# improved_circuit.net
KiCad netlist of a schematic drawn in EAGLE
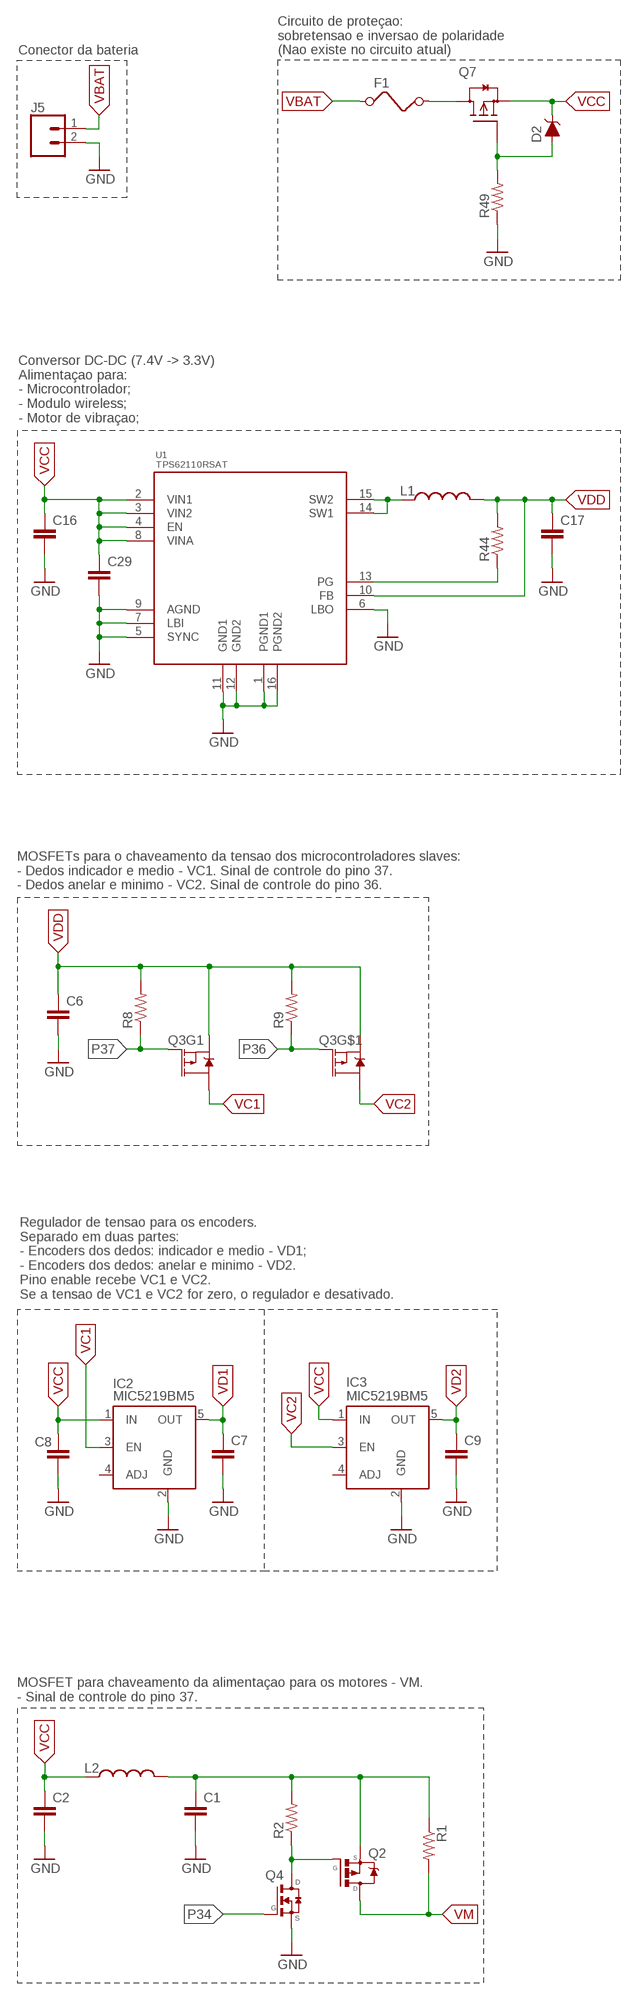
[diagram p0: schematic, sheet 1, part 1 of 2]
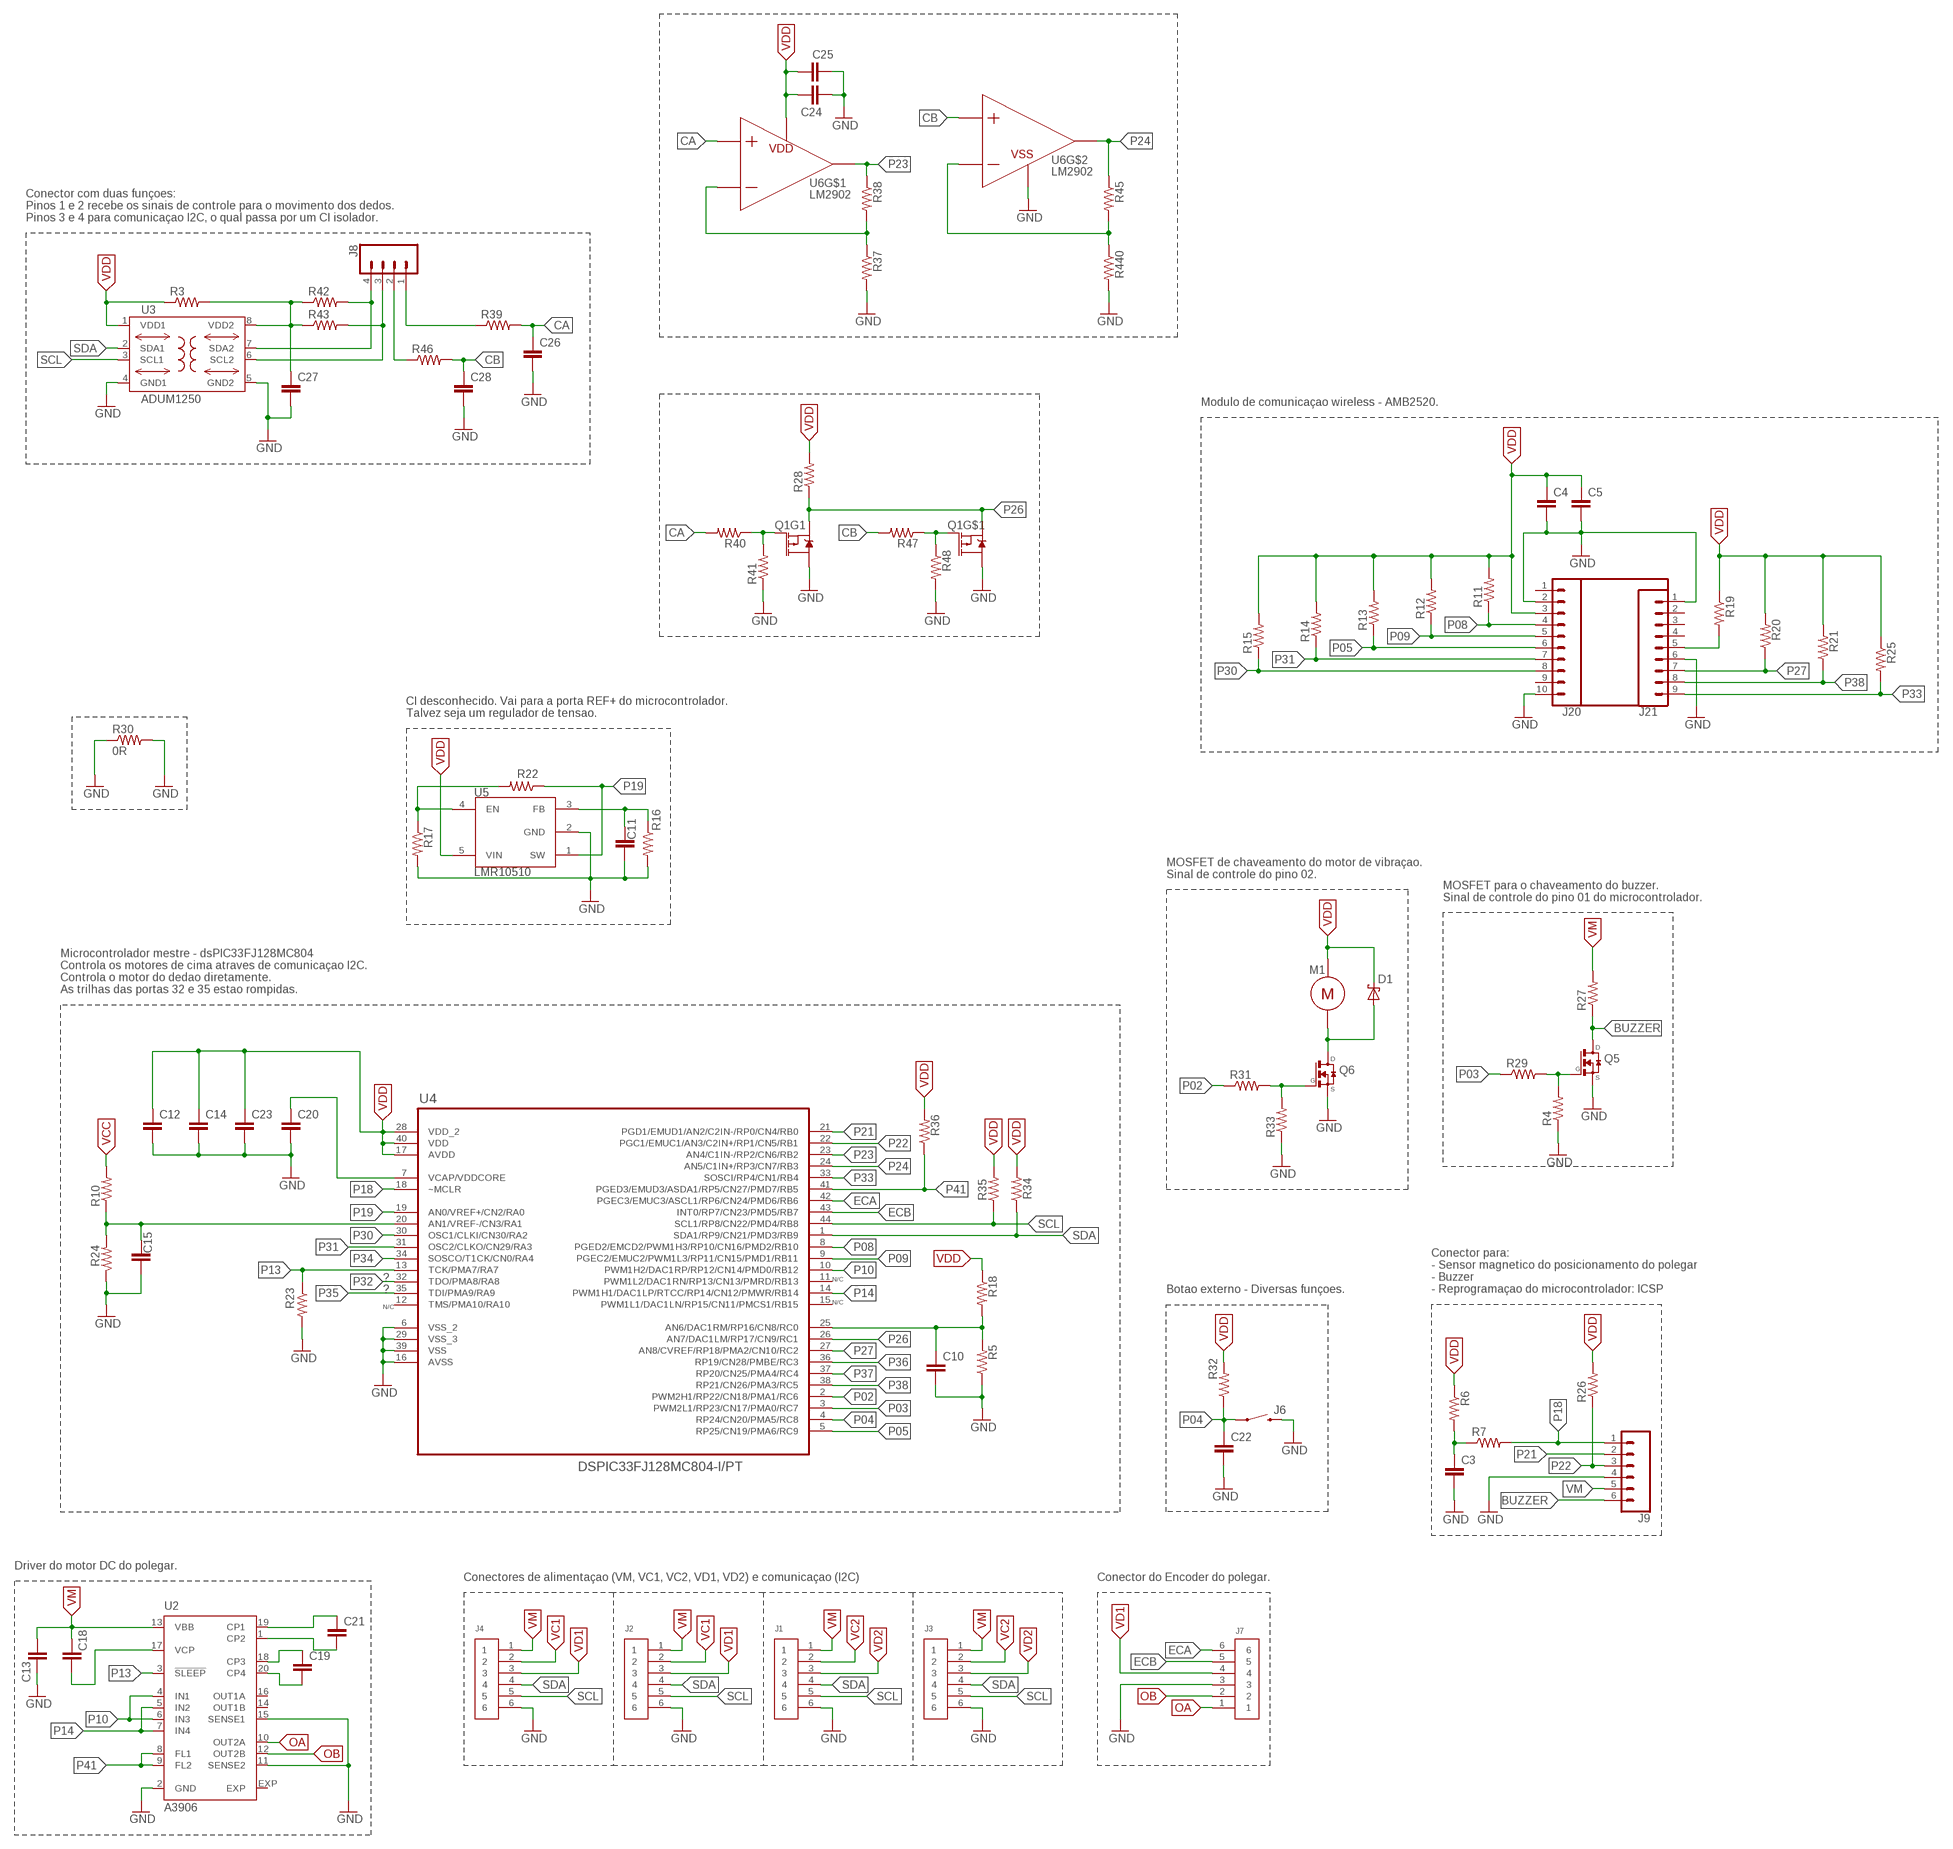
[diagram p1: schematic, sheet 1, part 2 of 2]

(export (version "E")
  (design (tool "Eeschema 10.0.6"))
  (components
    (comp (ref "C1")
      (value "C-EUC0805")
      (footprint "eagle-import:C0805")
      (libsource (lib "eagle-import") (part "C-EUC0805"))
    )
    (comp (ref "C2")
      (value "C-EUC0805")
      (footprint "eagle-import:C0805")
      (libsource (lib "eagle-import") (part "C-EUC0805"))
    )
    (comp (ref "C3")
      (value "CAPACITOR_0805_M")
      (footprint "eagle-import:RESC0805_M")
      (libsource (lib "eagle-import") (part "CAPACITOR_0805_M"))
    )
    (comp (ref "C4")
      (value "CAPACITOR_0805_M")
      (footprint "eagle-import:RESC0805_M")
      (libsource (lib "eagle-import") (part "CAPACITOR_0805_M"))
    )
    (comp (ref "C5")
      (value "CAPACITOR_0805_M")
      (footprint "eagle-import:RESC0805_M")
      (libsource (lib "eagle-import") (part "CAPACITOR_0805_M"))
    )
    (comp (ref "C6")
      (value "C-EUC0805")
      (footprint "eagle-import:C0805")
      (libsource (lib "eagle-import") (part "C-EUC0805"))
    )
    (comp (ref "C7")
      (value "CAPACITOR_0805_M")
      (footprint "eagle-import:RESC0805_M")
      (libsource (lib "eagle-import") (part "CAPACITOR_0805_M"))
    )
    (comp (ref "C8")
      (value "CAPACITOR_0805_M")
      (footprint "eagle-import:RESC0805_M")
      (libsource (lib "eagle-import") (part "CAPACITOR_0805_M"))
    )
    (comp (ref "C9")
      (value "CAPACITOR_0805_M")
      (footprint "eagle-import:RESC0805_M")
      (libsource (lib "eagle-import") (part "CAPACITOR_0805_M"))
    )
    (comp (ref "C10")
      (value "CAPACITOR_0805_M")
      (footprint "eagle-import:RESC0805_M")
      (libsource (lib "eagle-import") (part "CAPACITOR_0805_M"))
    )
    (comp (ref "C11")
      (value "CAPACITOR_0805_M")
      (footprint "eagle-import:RESC0805_M")
      (libsource (lib "eagle-import") (part "CAPACITOR_0805_M"))
    )
    (comp (ref "C12")
      (value "CAPACITOR_0805_M")
      (footprint "eagle-import:RESC0805_M")
      (libsource (lib "eagle-import") (part "CAPACITOR_0805_M"))
    )
    (comp (ref "C13")
      (value "CAPACITOR_0805_M")
      (footprint "eagle-import:RESC0805_M")
      (libsource (lib "eagle-import") (part "CAPACITOR_0805_M"))
    )
    (comp (ref "C14")
      (value "CAPACITOR_0805_M")
      (footprint "eagle-import:RESC0805_M")
      (libsource (lib "eagle-import") (part "CAPACITOR_0805_M"))
    )
    (comp (ref "C15")
      (value "CAPACITOR_0805_M")
      (footprint "eagle-import:RESC0805_M")
      (libsource (lib "eagle-import") (part "CAPACITOR_0805_M"))
    )
    (comp (ref "C16")
      (value "CAPACITOR_0805_M")
      (footprint "eagle-import:RESC0805_M")
      (libsource (lib "eagle-import") (part "CAPACITOR_0805_M"))
    )
    (comp (ref "C17")
      (value "CAPACITOR_0805_M")
      (footprint "eagle-import:RESC0805_M")
      (libsource (lib "eagle-import") (part "CAPACITOR_0805_M"))
    )
    (comp (ref "C18")
      (value "CAPACITOR_0805_M")
      (footprint "eagle-import:RESC0805_M")
      (libsource (lib "eagle-import") (part "CAPACITOR_0805_M"))
    )
    (comp (ref "C19")
      (value "CAPACITOR_0805_M")
      (footprint "eagle-import:RESC0805_M")
      (libsource (lib "eagle-import") (part "CAPACITOR_0805_M"))
    )
    (comp (ref "C20")
      (value "CAPACITOR_0805_M")
      (footprint "eagle-import:RESC0805_M")
      (libsource (lib "eagle-import") (part "CAPACITOR_0805_M"))
    )
    (comp (ref "C21")
      (value "CAPACITOR_0805_M")
      (footprint "eagle-import:RESC0805_M")
      (libsource (lib "eagle-import") (part "CAPACITOR_0805_M"))
    )
    (comp (ref "C22")
      (value "CAPACITOR_0805_M")
      (footprint "eagle-import:RESC0805_M")
      (libsource (lib "eagle-import") (part "CAPACITOR_0805_M"))
    )
    (comp (ref "C23")
      (value "CAPACITOR_0805_M")
      (footprint "eagle-import:RESC0805_M")
      (libsource (lib "eagle-import") (part "CAPACITOR_0805_M"))
    )
    (comp (ref "C24")
      (value "CAPACITOR_0805_M")
      (footprint "eagle-import:RESC0805_M")
      (libsource (lib "eagle-import") (part "CAPACITOR_0805_M"))
    )
    (comp (ref "C25")
      (value "CAPACITOR_0805_M")
      (footprint "eagle-import:RESC0805_M")
      (libsource (lib "eagle-import") (part "CAPACITOR_0805_M"))
    )
    (comp (ref "C26")
      (value "CAPACITOR_0805_M")
      (footprint "eagle-import:RESC0805_M")
      (libsource (lib "eagle-import") (part "CAPACITOR_0805_M"))
    )
    (comp (ref "C27")
      (value "CAPACITOR_0805_M")
      (footprint "eagle-import:RESC0805_M")
      (libsource (lib "eagle-import") (part "CAPACITOR_0805_M"))
    )
    (comp (ref "C28")
      (value "CAPACITOR_0805_M")
      (footprint "eagle-import:RESC0805_M")
      (libsource (lib "eagle-import") (part "CAPACITOR_0805_M"))
    )
    (comp (ref "C29")
      (value "CAPACITOR_0805_M")
      (footprint "eagle-import:RESC0805_M")
      (libsource (lib "eagle-import") (part "CAPACITOR_0805_M"))
    )
    (comp (ref "D1")
      (value "BAS70W,115")
      (footprint "eagle-import:SOT323")
      (fields (field (name "MF") "Nexperia USA"))
      (libsource (lib "eagle-import") (part "BAS70W,115"))
    )
    (comp (ref "D2")
      (value "3.6V")
      (footprint "eagle-import:SOD-323")
      (libsource (lib "eagle-import") (part "DIODE-ZENER-BZT52C3V6S"))
    )
    (comp (ref "F1")
      (value "FUSEF")
      (footprint "eagle-import:1812")
      (libsource (lib "eagle-import") (part "FUSEF"))
    )
    (comp (ref "IC2")
      (value "MIC5219BM5")
      (footprint "eagle-import:SOT23-5")
      (fields (field (name "MF") "ALTERA CORPORATION") (field (name "MPN") "MIC5219BM5 TR"))
      (libsource (lib "eagle-import") (part "MIC5219BM5"))
    )
    (comp (ref "IC3")
      (value "MIC5219BM5")
      (footprint "eagle-import:SOT23-5")
      (fields (field (name "MF") "ALTERA CORPORATION") (field (name "MPN") "MIC5219BM5 TR"))
      (libsource (lib "eagle-import") (part "MIC5219BM5"))
    )
    (comp (ref "J1")
      (value "61300611121")
      (footprint "eagle-import:61300611121")
      (fields
        (field (name "DIGI_KEY_PART_NUMBER") "732-5319-ND")
        (field (name "MANUFACTURER") "Wurth Electronics Inc.")
        (field (name "CREATED_BY") "PCBLayout.com")
      )
      (libsource (lib "eagle-import") (part "61300611121"))
    )
    (comp (ref "J2")
      (value "61300611121")
      (footprint "eagle-import:61300611121")
      (fields
        (field (name "DIGI_KEY_PART_NUMBER") "732-5319-ND")
        (field (name "MANUFACTURER") "Wurth Electronics Inc.")
        (field (name "CREATED_BY") "PCBLayout.com")
      )
      (libsource (lib "eagle-import") (part "61300611121"))
    )
    (comp (ref "J3")
      (value "61300611121")
      (footprint "eagle-import:61300611121")
      (fields
        (field (name "DIGI_KEY_PART_NUMBER") "732-5319-ND")
        (field (name "MANUFACTURER") "Wurth Electronics Inc.")
        (field (name "CREATED_BY") "PCBLayout.com")
      )
      (libsource (lib "eagle-import") (part "61300611121"))
    )
    (comp (ref "J4")
      (value "61300611121")
      (footprint "eagle-import:61300611121")
      (fields
        (field (name "DIGI_KEY_PART_NUMBER") "732-5319-ND")
        (field (name "MANUFACTURER") "Wurth Electronics Inc.")
        (field (name "CREATED_BY") "PCBLayout.com")
      )
      (libsource (lib "eagle-import") (part "61300611121"))
    )
    (comp (ref "J5")
      (value "CONN_02-JST-2MM-SMT")
      (footprint "eagle-import:JST-2-SMD")
      (libsource (lib "eagle-import") (part "CONN_02-JST-2MM-SMT"))
    )
    (comp (ref "J6")
      (value "RS032G05A3SM-SPST-MOMENTARY-SWSMD-1101NE")
      (footprint "eagle-import:TACTILE-SWITCH-1101NE")
      (libsource (lib "eagle-import") (part "RS032G05A3SM-SPST-MOMENTARY-SWSMD-1101NE"))
    )
    (comp (ref "J7")
      (value "61300611121")
      (footprint "eagle-import:61300611121")
      (fields
        (field (name "DIGI_KEY_PART_NUMBER") "732-5319-ND")
        (field (name "MANUFACTURER") "Wurth Electronics Inc.")
        (field (name "CREATED_BY") "PCBLayout.com")
      )
      (libsource (lib "eagle-import") (part "61300611121"))
    )
    (comp (ref "J8")
      (value "CONN_04SMD2")
      (footprint "eagle-import:1X04_1MM_RA")
      (libsource (lib "eagle-import") (part "CONN_04SMD2"))
    )
    (comp (ref "J9")
      (value "CONN_06SMD-1MM")
      (footprint "eagle-import:1X06-1MM")
      (libsource (lib "eagle-import") (part "CONN_06SMD-1MM"))
    )
    (comp (ref "J20")
      (value "CONN_10\"")
      (footprint "eagle-import:1X10")
      (libsource (lib "eagle-import") (part "CONN_10{dblquote}"))
    )
    (comp (ref "J21")
      (value "CONN_09")
      (footprint "eagle-import:1X09")
      (libsource (lib "eagle-import") (part "CONN_09"))
    )
    (comp (ref "L1")
      (value "INDUCTOR")
      (footprint "eagle-import:L0603")
      (libsource (lib "eagle-import") (part "INDUCTOR"))
    )
    (comp (ref "L2")
      (value "INDUCTOR")
      (footprint "eagle-import:L0603")
      (libsource (lib "eagle-import") (part "INDUCTOR"))
    )
    (comp (ref "M1")
      (value "308-100")
      (footprint "eagle-import:308-100")
      (libsource (lib "eagle-import") (part "308-100"))
    )
    (comp (ref "Q1")
      (value "2A/20V/150mΩ")
      (footprint "eagle-import:SOT26")
      (libsource (lib "eagle-import") (part "MOSFET_PCH_DUAL-DMP2240UDM"))
    )
    (comp (ref "Q2")
      (value "FDS6675")
      (footprint "eagle-import:SO08-E3")
      (fields (field (name "MF") "ON Semiconductor"))
      (libsource (lib "eagle-import") (part "FDS6675"))
    )
    (comp (ref "Q3")
      (value "2A/20V/150mΩ")
      (footprint "eagle-import:SOT26")
      (libsource (lib "eagle-import") (part "MOSFET_PCH_DUAL-DMP2240UDM"))
    )
    (comp (ref "Q4")
      (value "FDV303N")
      (footprint "eagle-import:SOT23")
      (fields (field (name "MF") "Fairchild Semiconductor") (field (name "MP") "FDV303N."))
      (libsource (lib "eagle-import") (part "FDV303N"))
    )
    (comp (ref "Q5")
      (value "FDV303N")
      (footprint "eagle-import:SOT23")
      (fields (field (name "MF") "Fairchild Semiconductor") (field (name "MP") "FDV303N."))
      (libsource (lib "eagle-import") (part "FDV303N"))
    )
    (comp (ref "Q6")
      (value "FDV303N")
      (footprint "eagle-import:SOT23")
      (fields (field (name "MF") "Fairchild Semiconductor") (field (name "MP") "FDV303N."))
      (libsource (lib "eagle-import") (part "FDV303N"))
    )
    (comp (ref "Q7")
      (value "BSS84LT1")
      (footprint "eagle-import:SOT23")
      (libsource (lib "eagle-import") (part "BSS84LT1"))
    )
    (comp (ref "R1")
      (value "R-US_M0805")
      (footprint "eagle-import:M0805")
      (libsource (lib "eagle-import") (part "R-US_M0805"))
    )
    (comp (ref "R2")
      (value "R-US_M0805")
      (footprint "eagle-import:M0805")
      (libsource (lib "eagle-import") (part "R-US_M0805"))
    )
    (comp (ref "R3")
      (value "R-US_M0805")
      (footprint "eagle-import:M0805")
      (libsource (lib "eagle-import") (part "R-US_M0805"))
    )
    (comp (ref "R4")
      (value "R-US_M0805")
      (footprint "eagle-import:M0805")
      (libsource (lib "eagle-import") (part "R-US_M0805"))
    )
    (comp (ref "R5")
      (value "R-US_M0805")
      (footprint "eagle-import:M0805")
      (libsource (lib "eagle-import") (part "R-US_M0805"))
    )
    (comp (ref "R6")
      (value "R-US_M0805")
      (footprint "eagle-import:M0805")
      (libsource (lib "eagle-import") (part "R-US_M0805"))
    )
    (comp (ref "R7")
      (value "R-US_M0805")
      (footprint "eagle-import:M0805")
      (libsource (lib "eagle-import") (part "R-US_M0805"))
    )
    (comp (ref "R8")
      (value "R-US_M0805")
      (footprint "eagle-import:M0805")
      (libsource (lib "eagle-import") (part "R-US_M0805"))
    )
    (comp (ref "R9")
      (value "R-US_M0805")
      (footprint "eagle-import:M0805")
      (libsource (lib "eagle-import") (part "R-US_M0805"))
    )
    (comp (ref "R10")
      (value "R-US_M0805")
      (footprint "eagle-import:M0805")
      (libsource (lib "eagle-import") (part "R-US_M0805"))
    )
    (comp (ref "R11")
      (value "R-US_M0805")
      (footprint "eagle-import:M0805")
      (libsource (lib "eagle-import") (part "R-US_M0805"))
    )
    (comp (ref "R12")
      (value "R-US_M0805")
      (footprint "eagle-import:M0805")
      (libsource (lib "eagle-import") (part "R-US_M0805"))
    )
    (comp (ref "R13")
      (value "R-US_M0805")
      (footprint "eagle-import:M0805")
      (libsource (lib "eagle-import") (part "R-US_M0805"))
    )
    (comp (ref "R14")
      (value "R-US_M0805")
      (footprint "eagle-import:M0805")
      (libsource (lib "eagle-import") (part "R-US_M0805"))
    )
    (comp (ref "R15")
      (value "R-US_M0805")
      (footprint "eagle-import:M0805")
      (libsource (lib "eagle-import") (part "R-US_M0805"))
    )
    (comp (ref "R16")
      (value "R-US_R0805")
      (footprint "eagle-import:R0805")
      (libsource (lib "eagle-import") (part "R-US_R0805"))
    )
    (comp (ref "R17")
      (value "R-US_R0805")
      (footprint "eagle-import:R0805")
      (libsource (lib "eagle-import") (part "R-US_R0805"))
    )
    (comp (ref "R18")
      (value "R-US_M0805")
      (footprint "eagle-import:M0805")
      (libsource (lib "eagle-import") (part "R-US_M0805"))
    )
    (comp (ref "R19")
      (value "R-US_M0805")
      (footprint "eagle-import:M0805")
      (libsource (lib "eagle-import") (part "R-US_M0805"))
    )
    (comp (ref "R20")
      (value "R-US_M0805")
      (footprint "eagle-import:M0805")
      (libsource (lib "eagle-import") (part "R-US_M0805"))
    )
    (comp (ref "R21")
      (value "R-US_M0805")
      (footprint "eagle-import:M0805")
      (libsource (lib "eagle-import") (part "R-US_M0805"))
    )
    (comp (ref "R22")
      (value "R-US_R0805")
      (footprint "eagle-import:R0805")
      (libsource (lib "eagle-import") (part "R-US_R0805"))
    )
    (comp (ref "R23")
      (value "R-US_M0805")
      (footprint "eagle-import:M0805")
      (libsource (lib "eagle-import") (part "R-US_M0805"))
    )
    (comp (ref "R24")
      (value "R-US_M0805")
      (footprint "eagle-import:M0805")
      (libsource (lib "eagle-import") (part "R-US_M0805"))
    )
    (comp (ref "R25")
      (value "R-US_M0805")
      (footprint "eagle-import:M0805")
      (libsource (lib "eagle-import") (part "R-US_M0805"))
    )
    (comp (ref "R26")
      (value "R-US_M0805")
      (footprint "eagle-import:M0805")
      (libsource (lib "eagle-import") (part "R-US_M0805"))
    )
    (comp (ref "R27")
      (value "R-US_M0805")
      (footprint "eagle-import:M0805")
      (libsource (lib "eagle-import") (part "R-US_M0805"))
    )
    (comp (ref "R28")
      (value "R-US_M0805")
      (footprint "eagle-import:M0805")
      (libsource (lib "eagle-import") (part "R-US_M0805"))
    )
    (comp (ref "R29")
      (value "R-US_M0805")
      (footprint "eagle-import:M0805")
      (libsource (lib "eagle-import") (part "R-US_M0805"))
    )
    (comp (ref "R30")
      (value "0R")
      (footprint "eagle-import:M0805")
      (libsource (lib "eagle-import") (part "R-US_M0805"))
    )
    (comp (ref "R31")
      (value "R-US_M0805")
      (footprint "eagle-import:M0805")
      (libsource (lib "eagle-import") (part "R-US_M0805"))
    )
    (comp (ref "R32")
      (value "R-US_M0805")
      (footprint "eagle-import:M0805")
      (libsource (lib "eagle-import") (part "R-US_M0805"))
    )
    (comp (ref "R33")
      (value "R-US_M0805")
      (footprint "eagle-import:M0805")
      (libsource (lib "eagle-import") (part "R-US_M0805"))
    )
    (comp (ref "R34")
      (value "R-US_M0805")
      (footprint "eagle-import:M0805")
      (libsource (lib "eagle-import") (part "R-US_M0805"))
    )
    (comp (ref "R35")
      (value "R-US_M0805")
      (footprint "eagle-import:M0805")
      (libsource (lib "eagle-import") (part "R-US_M0805"))
    )
    (comp (ref "R36")
      (value "R-US_M0805")
      (footprint "eagle-import:M0805")
      (libsource (lib "eagle-import") (part "R-US_M0805"))
    )
    (comp (ref "R37")
      (value "R-US_M0805")
      (footprint "eagle-import:M0805")
      (libsource (lib "eagle-import") (part "R-US_M0805"))
    )
    (comp (ref "R38")
      (value "R-US_M0805")
      (footprint "eagle-import:M0805")
      (libsource (lib "eagle-import") (part "R-US_M0805"))
    )
    (comp (ref "R39")
      (value "R-US_M0805")
      (footprint "eagle-import:M0805")
      (libsource (lib "eagle-import") (part "R-US_M0805"))
    )
    (comp (ref "R40")
      (value "R-US_M0805")
      (footprint "eagle-import:M0805")
      (libsource (lib "eagle-import") (part "R-US_M0805"))
    )
    (comp (ref "R41")
      (value "R-US_M0805")
      (footprint "eagle-import:M0805")
      (libsource (lib "eagle-import") (part "R-US_M0805"))
    )
    (comp (ref "R42")
      (value "R-US_M0805")
      (footprint "eagle-import:M0805")
      (libsource (lib "eagle-import") (part "R-US_M0805"))
    )
    (comp (ref "R43")
      (value "R-US_M0805")
      (footprint "eagle-import:M0805")
      (libsource (lib "eagle-import") (part "R-US_M0805"))
    )
    (comp (ref "R44")
      (value "R-US_M0805")
      (footprint "eagle-import:M0805")
      (libsource (lib "eagle-import") (part "R-US_M0805"))
    )
    (comp (ref "R45")
      (value "R-US_M0805")
      (footprint "eagle-import:M0805")
      (libsource (lib "eagle-import") (part "R-US_M0805"))
    )
    (comp (ref "R46")
      (value "R-US_M0805")
      (footprint "eagle-import:M0805")
      (libsource (lib "eagle-import") (part "R-US_M0805"))
    )
    (comp (ref "R47")
      (value "R-US_M0805")
      (footprint "eagle-import:M0805")
      (libsource (lib "eagle-import") (part "R-US_M0805"))
    )
    (comp (ref "R48")
      (value "R-US_M0805")
      (footprint "eagle-import:M0805")
      (libsource (lib "eagle-import") (part "R-US_M0805"))
    )
    (comp (ref "R49")
      (value "R-US_M0805")
      (footprint "eagle-import:M0805")
      (libsource (lib "eagle-import") (part "R-US_M0805"))
    )
    (comp (ref "R440")
      (value "R-US_M0805")
      (footprint "eagle-import:M0805")
      (libsource (lib "eagle-import") (part "R-US_M0805"))
    )
    (comp (ref "U1")
      (value "TPS62110RSAT")
      (footprint "eagle-import:QFN16")
      (libsource (lib "eagle-import") (part "TPS62110RSAT"))
    )
    (comp (ref "U2")
      (value "A3906")
      (footprint "eagle-import:QFN20")
      (libsource (lib "eagle-import") (part "A3906"))
    )
    (comp (ref "U3")
      (value "ADUM1250")
      (footprint "eagle-import:SO8-COOL")
      (fields (field (name "MF") "Analog Devices"))
      (libsource (lib "eagle-import") (part "ADUM1250"))
    )
    (comp (ref "U4")
      (value "DSPIC33FJ128MC804-I/PT")
      (footprint "eagle-import:QFP80P1200X1200X120-44N")
      (fields (field (name "MF") "Microchip"))
      (libsource (lib "eagle-import") (part "DSPIC33FJ128MC804-I/PT"))
    )
    (comp (ref "U5")
      (value "LMR10510")
      (footprint "eagle-import:SOT-23-5")
      (fields
        (field (name "DIGIKEY_PART_NUMBER") "LMR10510YMFE/NOPBTR-ND")
        (field (name "MANUFACTURER") "Texas Instruments")
        (field (name "MPN") "LMR10510YMFE/NOPB")
        (field (name "CREATED_BY") "PCBLayout.com")
      )
      (libsource (lib "eagle-import") (part "LMR10510YMFE/NOPB"))
    )
    (comp (ref "U6")
      (value "LM2902")
      (footprint "eagle-import:TSSOP8")
      (libsource (lib "eagle-import") (part "LM2902"))
    )
  )
  (nets
    (net (code "1") (name "BUZZER") (class "Default")
      (node (ref "J9") (pin "6") (pinfunction "6_6") (pintype "passive"))
      (node (ref "Q5") (pin "3") (pinfunction "D_3") (pintype "passive"))
      (node (ref "R27") (pin "1") (pinfunction "1_1") (pintype "passive"))
    )
    (net (code "2") (name "CA") (class "Default")
      (node (ref "C26") (pin "1") (pinfunction "1_1") (pintype "passive"))
      (node (ref "R39") (pin "2") (pinfunction "2_2") (pintype "passive"))
      (node (ref "R40") (pin "2") (pinfunction "2_2") (pintype "passive"))
      (node (ref "U6") (pin "3") (pinfunction "P_3") (pintype "bidirectional"))
    )
    (net (code "3") (name "CB") (class "Default")
      (node (ref "C28") (pin "1") (pinfunction "1_1") (pintype "passive"))
      (node (ref "R46") (pin "2") (pinfunction "2_2") (pintype "passive"))
      (node (ref "R47") (pin "2") (pinfunction "2_2") (pintype "passive"))
      (node (ref "U6") (pin "5") (pinfunction "P1_5") (pintype "bidirectional"))
    )
    (net (code "4") (name "ECA") (class "Default")
      (node (ref "J7") (pin "6") (pinfunction "6_6") (pintype "passive"))
      (node (ref "U4") (pin "42") (pinfunction "PGEC3/EMUC3/ASCL1/RP6/CN24/PMD6/RB6_42") (pintype "bidirectional"))
    )
    (net (code "5") (name "ECB") (class "Default")
      (node (ref "J7") (pin "5") (pinfunction "5_5") (pintype "passive"))
      (node (ref "U4") (pin "43") (pinfunction "INT0/RP7/CN23/PMD5/RB7_43") (pintype "bidirectional"))
    )
    (net (code "6") (name "GND") (class "Default")
      (node (ref "C1") (pin "2") (pinfunction "2_2") (pintype "passive"))
      (node (ref "C10") (pin "2") (pinfunction "2_2") (pintype "passive"))
      (node (ref "C11") (pin "2") (pinfunction "2_2") (pintype "passive"))
      (node (ref "C12") (pin "2") (pinfunction "2_2") (pintype "passive"))
      (node (ref "C13") (pin "1") (pinfunction "1_1") (pintype "passive"))
      (node (ref "C14") (pin "2") (pinfunction "2_2") (pintype "passive"))
      (node (ref "C15") (pin "2") (pinfunction "2_2") (pintype "passive"))
      (node (ref "C16") (pin "2") (pinfunction "2_2") (pintype "passive"))
      (node (ref "C17") (pin "2") (pinfunction "2_2") (pintype "passive"))
      (node (ref "C2") (pin "2") (pinfunction "2_2") (pintype "passive"))
      (node (ref "C20") (pin "2") (pinfunction "2_2") (pintype "passive"))
      (node (ref "C22") (pin "2") (pinfunction "2_2") (pintype "passive"))
      (node (ref "C23") (pin "2") (pinfunction "2_2") (pintype "passive"))
      (node (ref "C24") (pin "2") (pinfunction "2_2") (pintype "passive"))
      (node (ref "C25") (pin "2") (pinfunction "2_2") (pintype "passive"))
      (node (ref "C26") (pin "2") (pinfunction "2_2") (pintype "passive"))
      (node (ref "C27") (pin "2") (pinfunction "2_2") (pintype "passive"))
      (node (ref "C28") (pin "2") (pinfunction "2_2") (pintype "passive"))
      (node (ref "C29") (pin "2") (pinfunction "2_2") (pintype "passive"))
      (node (ref "C3") (pin "2") (pinfunction "2_2") (pintype "passive"))
      (node (ref "C4") (pin "2") (pinfunction "2_2") (pintype "passive"))
      (node (ref "C5") (pin "2") (pinfunction "2_2") (pintype "passive"))
      (node (ref "C6") (pin "2") (pinfunction "2_2") (pintype "passive"))
      (node (ref "C7") (pin "2") (pinfunction "2_2") (pintype "passive"))
      (node (ref "C8") (pin "2") (pinfunction "2_2") (pintype "passive"))
      (node (ref "C9") (pin "2") (pinfunction "2_2") (pintype "passive"))
      (node (ref "IC2") (pin "2") (pinfunction "GND_2") (pintype "power_in"))
      (node (ref "IC3") (pin "2") (pinfunction "GND_2") (pintype "power_in"))
      (node (ref "J1") (pin "6") (pinfunction "6_6") (pintype "passive"))
      (node (ref "J2") (pin "6") (pinfunction "6_6") (pintype "passive"))
      (node (ref "J20") (pin "10") (pinfunction "10_10") (pintype "passive"))
      (node (ref "J20") (pin "2") (pinfunction "2_2") (pintype "passive"))
      (node (ref "J21") (pin "1") (pinfunction "1_1") (pintype "passive"))
      (node (ref "J21") (pin "6") (pinfunction "6_6") (pintype "passive"))
      (node (ref "J3") (pin "6") (pinfunction "6_6") (pintype "passive"))
      (node (ref "J4") (pin "6") (pinfunction "6_6") (pintype "passive"))
      (node (ref "J5") (pin "2") (pinfunction "1_2") (pintype "passive"))
      (node (ref "J6") (pin "2") (pinfunction "2_2") (pintype "passive"))
      (node (ref "J7") (pin "3") (pinfunction "3_3") (pintype "passive"))
      (node (ref "J9") (pin "4") (pinfunction "4_4") (pintype "passive"))
      (node (ref "Q1") (pin "D1") (pinfunction "D_D1") (pintype "bidirectional"))
      (node (ref "Q1") (pin "D2") (pinfunction "D_D2") (pintype "bidirectional"))
      (node (ref "Q4") (pin "2") (pinfunction "S_2") (pintype "passive"))
      (node (ref "Q5") (pin "2") (pinfunction "S_2") (pintype "passive"))
      (node (ref "Q6") (pin "2") (pinfunction "S_2") (pintype "passive"))
      (node (ref "R16") (pin "2") (pinfunction "2_2") (pintype "passive"))
      (node (ref "R17") (pin "2") (pinfunction "2_2") (pintype "passive"))
      (node (ref "R23") (pin "2") (pinfunction "2_2") (pintype "passive"))
      (node (ref "R24") (pin "1") (pinfunction "1_1") (pintype "passive"))
      (node (ref "R30") (pin "1") (pinfunction "1_1") (pintype "passive"))
      (node (ref "R30") (pin "2") (pinfunction "2_2") (pintype "passive"))
      (node (ref "R33") (pin "1") (pinfunction "1_1") (pintype "passive"))
      (node (ref "R37") (pin "2") (pinfunction "2_2") (pintype "passive"))
      (node (ref "R4") (pin "1") (pinfunction "1_1") (pintype "passive"))
      (node (ref "R41") (pin "1") (pinfunction "1_1") (pintype "passive"))
      (node (ref "R440") (pin "2") (pinfunction "2_2") (pintype "passive"))
      (node (ref "R48") (pin "2") (pinfunction "2_2") (pintype "passive"))
      (node (ref "R49") (pin "1") (pinfunction "1_1") (pintype "passive"))
      (node (ref "R5") (pin "1") (pinfunction "1_1") (pintype "passive"))
      (node (ref "U1") (pin "1") (pinfunction "PGND1_1") (pintype "input"))
      (node (ref "U1") (pin "11") (pinfunction "GND1_11") (pintype "input"))
      (node (ref "U1") (pin "12") (pinfunction "GND2_12") (pintype "input"))
      (node (ref "U1") (pin "16") (pinfunction "PGND2_16") (pintype "bidirectional"))
      (node (ref "U1") (pin "5") (pinfunction "SYNC_5") (pintype "input"))
      (node (ref "U1") (pin "6") (pinfunction "LBO_6") (pintype "bidirectional"))
      (node (ref "U1") (pin "7") (pinfunction "LBI_7") (pintype "input"))
      (node (ref "U1") (pin "9") (pinfunction "AGND_9") (pintype "input"))
      (node (ref "U2") (pin "11") (pinfunction "SENSE2_11") (pintype "input"))
      (node (ref "U2") (pin "15") (pinfunction "SENSE1_15") (pintype "input"))
      (node (ref "U2") (pin "2") (pinfunction "GND_2") (pintype "power_in"))
      (node (ref "U3") (pin "4") (pinfunction "GND1_4") (pintype "power_in"))
      (node (ref "U3") (pin "5") (pinfunction "GND2_5") (pintype "power_in"))
      (node (ref "U4") (pin "16") (pinfunction "AVSS_16") (pintype "passive"))
      (node (ref "U4") (pin "29") (pinfunction "VSS_3_29") (pintype "passive"))
      (node (ref "U4") (pin "39") (pinfunction "VSS_39") (pintype "passive"))
      (node (ref "U4") (pin "6") (pinfunction "VSS_2_6") (pintype "passive"))
      (node (ref "U5") (pin "2") (pinfunction "GND_2") (pintype "power_in"))
      (node (ref "U6") (pin "4") (pinfunction "VSS_4") (pintype "power_in"))
    )
    (net (code "7") (name "Net-(C3-Pad1)") (class "Default")
      (node (ref "C3") (pin "1") (pinfunction "1_1") (pintype "passive"))
      (node (ref "R6") (pin "2") (pinfunction "2_2") (pintype "passive"))
      (node (ref "R7") (pin "1") (pinfunction "1_1") (pintype "passive"))
    )
    (net (code "8") (name "Net-(D1-A)") (class "Default")
      (node (ref "D1") (pin "1") (pinfunction "A_1") (pintype "passive"))
      (node (ref "M1") (pin "NEG") (pinfunction "NEG_NEG") (pintype "bidirectional"))
      (node (ref "Q6") (pin "3") (pinfunction "D_3") (pintype "passive"))
    )
    (net (code "9") (name "Net-(J8-Pad1)") (class "Default")
      (node (ref "J8") (pin "1") (pinfunction "1_1") (pintype "passive"))
      (node (ref "R39") (pin "1") (pinfunction "1_1") (pintype "passive"))
    )
    (net (code "10") (name "Net-(J8-Pad2)") (class "Default")
      (node (ref "J8") (pin "2") (pinfunction "2_2") (pintype "passive"))
      (node (ref "R46") (pin "1") (pinfunction "1_1") (pintype "passive"))
    )
    (net (code "11") (name "Net-(J21-Pad5)") (class "Default")
      (node (ref "J21") (pin "5") (pinfunction "5_5") (pintype "passive"))
      (node (ref "R19") (pin "2") (pinfunction "2_2") (pintype "passive"))
    )
    (net (code "12") (name "Net-(Q1A-G)") (class "Default")
      (node (ref "Q1") (pin "G2") (pinfunction "G_G2") (pintype "bidirectional"))
      (node (ref "R47") (pin "1") (pinfunction "1_1") (pintype "passive"))
      (node (ref "R48") (pin "1") (pinfunction "1_1") (pintype "passive"))
    )
    (net (code "13") (name "Net-(Q1B-G)") (class "Default")
      (node (ref "Q1") (pin "G1") (pinfunction "G_G1") (pintype "bidirectional"))
      (node (ref "R40") (pin "1") (pinfunction "1_1") (pintype "passive"))
      (node (ref "R41") (pin "2") (pinfunction "2_2") (pintype "passive"))
    )
    (net (code "14") (name "Net-(Q2-G)") (class "Default")
      (node (ref "Q2") (pin "4") (pinfunction "G_4") (pintype "passive"))
      (node (ref "Q4") (pin "3") (pinfunction "D_3") (pintype "passive"))
      (node (ref "R2") (pin "1") (pinfunction "1_1") (pintype "passive"))
    )
    (net (code "15") (name "Net-(Q2-S)") (class "Default")
      (node (ref "C1") (pin "1") (pinfunction "1_1") (pintype "passive"))
      (node (ref "L2") (pin "2") (pinfunction "2_2") (pintype "passive"))
      (node (ref "Q2") (pin "1-3") (pinfunction "S_1-3") (pintype "passive"))
      (node (ref "R1") (pin "1") (pinfunction "1_1") (pintype "passive"))
      (node (ref "R2") (pin "2") (pinfunction "2_2") (pintype "passive"))
    )
    (net (code "16") (name "Net-(Q5-G)") (class "Default")
      (node (ref "Q5") (pin "1") (pinfunction "G_1") (pintype "passive"))
      (node (ref "R29") (pin "2") (pinfunction "2_2") (pintype "passive"))
      (node (ref "R4") (pin "2") (pinfunction "2_2") (pintype "passive"))
    )
    (net (code "17") (name "Net-(Q6-G)") (class "Default")
      (node (ref "Q6") (pin "1") (pinfunction "G_1") (pintype "passive"))
      (node (ref "R31") (pin "2") (pinfunction "2_2") (pintype "passive"))
      (node (ref "R33") (pin "2") (pinfunction "2_2") (pintype "passive"))
    )
    (net (code "18") (name "Net-(Q7-D)") (class "Default")
      (node (ref "F1") (pin "2") (pinfunction "2_2") (pintype "passive"))
      (node (ref "Q7") (pin "3") (pinfunction "D_3") (pintype "passive"))
    )
    (net (code "19") (name "Net-(Q7-G)") (class "Default")
      (node (ref "D2") (pin "A") (pinfunction "A_A") (pintype "passive"))
      (node (ref "Q7") (pin "1") (pinfunction "G_1") (pintype "passive"))
      (node (ref "R49") (pin "2") (pinfunction "2_2") (pintype "passive"))
    )
    (net (code "20") (name "Net-(U1-PG)") (class "Default")
      (node (ref "R44") (pin "1") (pinfunction "1_1") (pintype "passive"))
      (node (ref "U1") (pin "13") (pinfunction "PG_13") (pintype "bidirectional"))
    )
    (net (code "21") (name "Net-(U1-SW1)") (class "Default")
      (node (ref "L1") (pin "1") (pinfunction "1_1") (pintype "passive"))
      (node (ref "U1") (pin "14") (pinfunction "SW1_14") (pintype "output"))
      (node (ref "U1") (pin "15") (pinfunction "SW2_15") (pintype "output"))
    )
    (net (code "22") (name "Net-(U2-CP1)") (class "Default")
      (node (ref "C21") (pin "1") (pinfunction "1_1") (pintype "passive"))
      (node (ref "U2") (pin "19") (pinfunction "CP1_19") (pintype "passive"))
    )
    (net (code "23") (name "Net-(U2-CP2)") (class "Default")
      (node (ref "C21") (pin "2") (pinfunction "2_2") (pintype "passive"))
      (node (ref "U2") (pin "1") (pinfunction "CP2_1") (pintype "passive"))
    )
    (net (code "24") (name "Net-(U2-CP3)") (class "Default")
      (node (ref "C19") (pin "1") (pinfunction "1_1") (pintype "passive"))
      (node (ref "U2") (pin "18") (pinfunction "CP3_18") (pintype "passive"))
    )
    (net (code "25") (name "Net-(U2-CP4)") (class "Default")
      (node (ref "C19") (pin "2") (pinfunction "2_2") (pintype "passive"))
      (node (ref "U2") (pin "20") (pinfunction "CP4_20") (pintype "passive"))
    )
    (net (code "26") (name "Net-(U2-VCP)") (class "Default")
      (node (ref "C18") (pin "2") (pinfunction "2_2") (pintype "passive"))
      (node (ref "U2") (pin "17") (pinfunction "VCP_17") (pintype "passive"))
    )
    (net (code "27") (name "Net-(U3-SCL2)") (class "Default")
      (node (ref "J8") (pin "3") (pinfunction "3_3") (pintype "passive"))
      (node (ref "R43") (pin "2") (pinfunction "2_2") (pintype "passive"))
      (node (ref "U3") (pin "6") (pinfunction "SCL2_6") (pintype "bidirectional"))
    )
    (net (code "28") (name "Net-(U3-SDA2)") (class "Default")
      (node (ref "J8") (pin "4") (pinfunction "4_4") (pintype "passive"))
      (node (ref "R42") (pin "2") (pinfunction "2_2") (pintype "passive"))
      (node (ref "U3") (pin "7") (pinfunction "SDA2_7") (pintype "bidirectional"))
    )
    (net (code "29") (name "Net-(U3-VDD2)") (class "Default")
      (node (ref "C27") (pin "1") (pinfunction "1_1") (pintype "passive"))
      (node (ref "R3") (pin "2") (pinfunction "2_2") (pintype "passive"))
      (node (ref "R42") (pin "1") (pinfunction "1_1") (pintype "passive"))
      (node (ref "R43") (pin "1") (pinfunction "1_1") (pintype "passive"))
      (node (ref "U3") (pin "8") (pinfunction "VDD2_8") (pintype "power_in"))
    )
    (net (code "30") (name "Net-(U4-AN1{slash}VREF-{slash}CN3{slash}RA1)") (class "Default")
      (node (ref "C15") (pin "1") (pinfunction "1_1") (pintype "passive"))
      (node (ref "R10") (pin "1") (pinfunction "1_1") (pintype "passive"))
      (node (ref "R24") (pin "2") (pinfunction "2_2") (pintype "passive"))
      (node (ref "U4") (pin "20") (pinfunction "AN1/VREF-/CN3/RA1_20") (pintype "bidirectional"))
    )
    (net (code "31") (name "Net-(U4-AN6{slash}DAC1RM{slash}RP16{slash}CN8{slash}RC0)") (class "Default")
      (node (ref "C10") (pin "1") (pinfunction "1_1") (pintype "passive"))
      (node (ref "R18") (pin "2") (pinfunction "2_2") (pintype "passive"))
      (node (ref "R5") (pin "2") (pinfunction "2_2") (pintype "passive"))
      (node (ref "U4") (pin "25") (pinfunction "AN6/DAC1RM/RP16/CN8/RC0_25") (pintype "bidirectional"))
    )
    (net (code "32") (name "Net-(U4-VCAP{slash}VDDCORE)") (class "Default")
      (node (ref "C20") (pin "1") (pinfunction "1_1") (pintype "passive"))
      (node (ref "U4") (pin "7") (pinfunction "VCAP/VDDCORE_7") (pintype "power_in"))
    )
    (net (code "33") (name "Net-(U5-EN)") (class "Default")
      (node (ref "R17") (pin "1") (pinfunction "1_1") (pintype "passive"))
      (node (ref "R22") (pin "2") (pinfunction "2_2") (pintype "passive"))
      (node (ref "U5") (pin "4") (pinfunction "EN_4") (pintype "input"))
    )
    (net (code "34") (name "Net-(U5-FB)") (class "Default")
      (node (ref "C11") (pin "1") (pinfunction "1_1") (pintype "passive"))
      (node (ref "R16") (pin "1") (pinfunction "1_1") (pintype "passive"))
      (node (ref "U5") (pin "3") (pinfunction "FB_3") (pintype "output"))
    )
    (net (code "35") (name "Net-(U6A-N)") (class "Default")
      (node (ref "R37") (pin "1") (pinfunction "1_1") (pintype "passive"))
      (node (ref "R38") (pin "2") (pinfunction "2_2") (pintype "passive"))
      (node (ref "U6") (pin "2") (pinfunction "N_2") (pintype "bidirectional"))
    )
    (net (code "36") (name "Net-(U6B-N1)") (class "Default")
      (node (ref "R440") (pin "1") (pinfunction "1_1") (pintype "passive"))
      (node (ref "R45") (pin "2") (pinfunction "2_2") (pintype "passive"))
      (node (ref "U6") (pin "6") (pinfunction "N1_6") (pintype "bidirectional"))
    )
    (net (code "37") (name "OA") (class "Default")
      (node (ref "J7") (pin "1") (pinfunction "1_1") (pintype "passive"))
      (node (ref "U2") (pin "10") (pinfunction "OUT2A_10") (pintype "output"))
    )
    (net (code "38") (name "OB") (class "Default")
      (node (ref "J7") (pin "2") (pinfunction "2_2") (pintype "passive"))
      (node (ref "U2") (pin "12") (pinfunction "OUT2B_12") (pintype "output"))
    )
    (net (code "39") (name "P02") (class "Default")
      (node (ref "R31") (pin "1") (pinfunction "1_1") (pintype "passive"))
      (node (ref "U4") (pin "2") (pinfunction "PWM2H1/RP22/CN18/PMA1/RC6_2") (pintype "bidirectional"))
    )
    (net (code "40") (name "P03") (class "Default")
      (node (ref "R29") (pin "1") (pinfunction "1_1") (pintype "passive"))
      (node (ref "U4") (pin "3") (pinfunction "PWM2L1/RP23/CN17/PMA0/RC7_3") (pintype "bidirectional"))
    )
    (net (code "41") (name "P04") (class "Default")
      (node (ref "C22") (pin "1") (pinfunction "1_1") (pintype "passive"))
      (node (ref "J6") (pin "1") (pinfunction "1_1") (pintype "passive"))
      (node (ref "R32") (pin "1") (pinfunction "1_1") (pintype "passive"))
      (node (ref "U4") (pin "4") (pinfunction "RP24/CN20/PMA5/RC8_4") (pintype "bidirectional"))
    )
    (net (code "42") (name "P05") (class "Default")
      (node (ref "J20") (pin "6") (pinfunction "6_6") (pintype "passive"))
      (node (ref "R13") (pin "1") (pinfunction "1_1") (pintype "passive"))
      (node (ref "U4") (pin "5") (pinfunction "RP25/CN19/PMA6/RC9_5") (pintype "bidirectional"))
    )
    (net (code "43") (name "P08") (class "Default")
      (node (ref "J20") (pin "4") (pinfunction "4_4") (pintype "passive"))
      (node (ref "R11") (pin "1") (pinfunction "1_1") (pintype "passive"))
      (node (ref "U4") (pin "8") (pinfunction "PGED2/EMCD2/PWM1H3/RP10/CN16/PMD2/RB10_8") (pintype "bidirectional"))
    )
    (net (code "44") (name "P09") (class "Default")
      (node (ref "J20") (pin "5") (pinfunction "5_5") (pintype "passive"))
      (node (ref "R12") (pin "1") (pinfunction "1_1") (pintype "passive"))
      (node (ref "U4") (pin "9") (pinfunction "PGEC2/EMUC2/PWM1L3/RP11/CN15/PMD1/RB11_9") (pintype "bidirectional"))
    )
    (net (code "45") (name "P10") (class "Default")
      (node (ref "U2") (pin "4") (pinfunction "IN1_4") (pintype "input"))
      (node (ref "U2") (pin "6") (pinfunction "IN3_6") (pintype "input"))
      (node (ref "U4") (pin "10") (pinfunction "PWM1H2/DAC1RP/RP12/CN14/PMD0/RB12_10") (pintype "bidirectional"))
    )
    (net (code "46") (name "P13") (class "Default")
      (node (ref "R23") (pin "1") (pinfunction "1_1") (pintype "passive"))
      (node (ref "U2") (pin "3") (pinfunction "~{SLEEP}_3") (pintype "input"))
      (node (ref "U4") (pin "13") (pinfunction "TCK/PMA7/RA7_13") (pintype "bidirectional"))
    )
    (net (code "47") (name "P14") (class "Default")
      (node (ref "U2") (pin "5") (pinfunction "IN2_5") (pintype "input"))
      (node (ref "U2") (pin "7") (pinfunction "IN4_7") (pintype "input"))
      (node (ref "U4") (pin "14") (pinfunction "PWM1H1/DAC1LP/RTCC/RP14/CN12/PMWR/RB14_14") (pintype "bidirectional"))
    )
    (net (code "48") (name "P18") (class "Default")
      (node (ref "J9") (pin "1") (pinfunction "1_1") (pintype "passive"))
      (node (ref "R7") (pin "2") (pinfunction "2_2") (pintype "passive"))
      (node (ref "U4") (pin "18") (pinfunction "~{MCLR}_18") (pintype "input"))
    )
    (net (code "49") (name "P19") (class "Default")
      (node (ref "R22") (pin "1") (pinfunction "1_1") (pintype "passive"))
      (node (ref "U4") (pin "19") (pinfunction "AN0/VREF+/CN2/RA0_19") (pintype "bidirectional"))
      (node (ref "U5") (pin "1") (pinfunction "SW_1") (pintype "bidirectional"))
    )
    (net (code "50") (name "P21") (class "Default")
      (node (ref "J9") (pin "2") (pinfunction "2_2") (pintype "passive"))
      (node (ref "U4") (pin "21") (pinfunction "PGD1/EMUD1/AN2/C2IN-/RP0/CN4/RB0_21") (pintype "bidirectional"))
    )
    (net (code "51") (name "P22") (class "Default")
      (node (ref "J9") (pin "3") (pinfunction "3_3") (pintype "passive"))
      (node (ref "R26") (pin "1") (pinfunction "1_1") (pintype "passive"))
      (node (ref "U4") (pin "22") (pinfunction "PGC1/EMUC1/AN3/C2IN+/RP1/CN5/RB1_22") (pintype "bidirectional"))
    )
    (net (code "52") (name "P23") (class "Default")
      (node (ref "R38") (pin "1") (pinfunction "1_1") (pintype "passive"))
      (node (ref "U4") (pin "23") (pinfunction "AN4/C1IN-/RP2/CN6/RB2_23") (pintype "bidirectional"))
      (node (ref "U6") (pin "1") (pinfunction "VOUT_1") (pintype "bidirectional"))
    )
    (net (code "53") (name "P24") (class "Default")
      (node (ref "R45") (pin "1") (pinfunction "1_1") (pintype "passive"))
      (node (ref "U4") (pin "24") (pinfunction "AN5/C1IN+/RP3/CN7/RB3_24") (pintype "bidirectional"))
      (node (ref "U6") (pin "7") (pinfunction "VOUT1_7") (pintype "bidirectional"))
    )
    (net (code "54") (name "P26") (class "Default")
      (node (ref "Q1") (pin "S1") (pinfunction "S_S1") (pintype "bidirectional"))
      (node (ref "Q1") (pin "S2") (pinfunction "S_S2") (pintype "bidirectional"))
      (node (ref "R28") (pin "1") (pinfunction "1_1") (pintype "passive"))
      (node (ref "U4") (pin "26") (pinfunction "AN7/DAC1LM/RP17/CN9/RC1_26") (pintype "bidirectional"))
    )
    (net (code "55") (name "P27") (class "Default")
      (node (ref "J21") (pin "7") (pinfunction "7_7") (pintype "passive"))
      (node (ref "R20") (pin "1") (pinfunction "1_1") (pintype "passive"))
      (node (ref "U4") (pin "27") (pinfunction "AN8/CVREF/RP18/PMA2/CN10/RC2_27") (pintype "bidirectional"))
    )
    (net (code "56") (name "P30") (class "Default")
      (node (ref "J20") (pin "8") (pinfunction "8_8") (pintype "passive"))
      (node (ref "R15") (pin "1") (pinfunction "1_1") (pintype "passive"))
      (node (ref "U4") (pin "30") (pinfunction "OSC1/CLKI/CN30/RA2_30") (pintype "bidirectional"))
    )
    (net (code "57") (name "P31") (class "Default")
      (node (ref "J20") (pin "7") (pinfunction "7_7") (pintype "passive"))
      (node (ref "R14") (pin "1") (pinfunction "1_1") (pintype "passive"))
      (node (ref "U4") (pin "31") (pinfunction "OSC2/CLKO/CN29/RA3_31") (pintype "bidirectional"))
    )
    (net (code "58") (name "P32") (class "Default")
      (node (ref "U4") (pin "32") (pinfunction "TDO/PMA8/RA8_32") (pintype "bidirectional"))
    )
    (net (code "59") (name "P33") (class "Default")
      (node (ref "J21") (pin "9") (pinfunction "9_9") (pintype "passive"))
      (node (ref "R25") (pin "2") (pinfunction "2_2") (pintype "passive"))
      (node (ref "U4") (pin "33") (pinfunction "SOSCI/RP4/CN1/RB4_33") (pintype "bidirectional"))
    )
    (net (code "60") (name "P34") (class "Default")
      (node (ref "Q4") (pin "1") (pinfunction "G_1") (pintype "passive"))
      (node (ref "U4") (pin "34") (pinfunction "SOSCO/T1CK/CN0/RA4_34") (pintype "bidirectional"))
    )
    (net (code "61") (name "P35") (class "Default")
      (node (ref "U4") (pin "35") (pinfunction "TDI/PMA9/RA9_35") (pintype "bidirectional"))
    )
    (net (code "62") (name "P36") (class "Default")
      (node (ref "Q3") (pin "G2") (pinfunction "G_G2") (pintype "bidirectional"))
      (node (ref "R9") (pin "1") (pinfunction "1_1") (pintype "passive"))
      (node (ref "U4") (pin "36") (pinfunction "RP19/CN28/PMBE/RC3_36") (pintype "bidirectional"))
    )
    (net (code "63") (name "P37") (class "Default")
      (node (ref "Q3") (pin "G1") (pinfunction "G_G1") (pintype "bidirectional"))
      (node (ref "R8") (pin "1") (pinfunction "1_1") (pintype "passive"))
      (node (ref "U4") (pin "37") (pinfunction "RP20/CN25/PMA4/RC4_37") (pintype "bidirectional"))
    )
    (net (code "64") (name "P38") (class "Default")
      (node (ref "J21") (pin "8") (pinfunction "8_8") (pintype "passive"))
      (node (ref "R21") (pin "1") (pinfunction "1_1") (pintype "passive"))
      (node (ref "U4") (pin "38") (pinfunction "RP21/CN26/PMA3/RC5_38") (pintype "bidirectional"))
    )
    (net (code "65") (name "P41") (class "Default")
      (node (ref "R36") (pin "1") (pinfunction "1_1") (pintype "passive"))
      (node (ref "U2") (pin "8") (pinfunction "FL1_8") (pintype "input"))
      (node (ref "U2") (pin "9") (pinfunction "FL2_9") (pintype "input"))
      (node (ref "U4") (pin "41") (pinfunction "PGED3/EMUD3/ASDA1/RP5/CN27/PMD7/RB5_41") (pintype "bidirectional"))
    )
    (net (code "66") (name "SCL") (class "Default")
      (node (ref "J1") (pin "5") (pinfunction "5_5") (pintype "passive"))
      (node (ref "J2") (pin "5") (pinfunction "5_5") (pintype "passive"))
      (node (ref "J3") (pin "5") (pinfunction "5_5") (pintype "passive"))
      (node (ref "J4") (pin "5") (pinfunction "5_5") (pintype "passive"))
      (node (ref "R35") (pin "1") (pinfunction "1_1") (pintype "passive"))
      (node (ref "U3") (pin "3") (pinfunction "SCL1_3") (pintype "bidirectional"))
      (node (ref "U4") (pin "44") (pinfunction "SCL1/RP8/CN22/PMD4/RB8_44") (pintype "bidirectional"))
    )
    (net (code "67") (name "SDA") (class "Default")
      (node (ref "J1") (pin "4") (pinfunction "4_4") (pintype "passive"))
      (node (ref "J2") (pin "4") (pinfunction "4_4") (pintype "passive"))
      (node (ref "J3") (pin "4") (pinfunction "4_4") (pintype "passive"))
      (node (ref "J4") (pin "4") (pinfunction "4_4") (pintype "passive"))
      (node (ref "R34") (pin "1") (pinfunction "1_1") (pintype "passive"))
      (node (ref "U3") (pin "2") (pinfunction "SDA1_2") (pintype "bidirectional"))
      (node (ref "U4") (pin "1") (pinfunction "SDA1/RP9/CN21/PMD3/RB9_1") (pintype "bidirectional"))
    )
    (net (code "68") (name "VBAT") (class "Default")
      (node (ref "F1") (pin "1") (pinfunction "1_1") (pintype "passive"))
      (node (ref "J5") (pin "1") (pinfunction "2_1") (pintype "passive"))
    )
    (net (code "69") (name "VC1") (class "Default")
      (node (ref "IC2") (pin "3") (pinfunction "EN_3") (pintype "input"))
      (node (ref "J2") (pin "2") (pinfunction "2_2") (pintype "passive"))
      (node (ref "J4") (pin "2") (pinfunction "2_2") (pintype "passive"))
      (node (ref "Q3") (pin "D1") (pinfunction "D_D1") (pintype "bidirectional"))
    )
    (net (code "70") (name "VC2") (class "Default")
      (node (ref "IC3") (pin "3") (pinfunction "EN_3") (pintype "input"))
      (node (ref "J1") (pin "2") (pinfunction "2_2") (pintype "passive"))
      (node (ref "J3") (pin "2") (pinfunction "2_2") (pintype "passive"))
      (node (ref "Q3") (pin "D2") (pinfunction "D_D2") (pintype "bidirectional"))
    )
    (net (code "71") (name "VCC") (class "Default")
      (node (ref "C16") (pin "1") (pinfunction "1_1") (pintype "passive"))
      (node (ref "C2") (pin "1") (pinfunction "1_1") (pintype "passive"))
      (node (ref "C29") (pin "1") (pinfunction "1_1") (pintype "passive"))
      (node (ref "C8") (pin "1") (pinfunction "1_1") (pintype "passive"))
      (node (ref "D2") (pin "C") (pinfunction "C_C") (pintype "passive"))
      (node (ref "IC2") (pin "1") (pinfunction "IN_1") (pintype "input"))
      (node (ref "IC3") (pin "1") (pinfunction "IN_1") (pintype "input"))
      (node (ref "L2") (pin "1") (pinfunction "1_1") (pintype "passive"))
      (node (ref "Q7") (pin "2") (pinfunction "S_2") (pintype "passive"))
      (node (ref "R10") (pin "2") (pinfunction "2_2") (pintype "passive"))
      (node (ref "U1") (pin "2") (pinfunction "VIN1_2") (pintype "input"))
      (node (ref "U1") (pin "3") (pinfunction "VIN2_3") (pintype "input"))
      (node (ref "U1") (pin "4") (pinfunction "EN_4") (pintype "input"))
      (node (ref "U1") (pin "8") (pinfunction "VINA_8") (pintype "input"))
    )
    (net (code "72") (name "VD1") (class "Default")
      (node (ref "C7") (pin "1") (pinfunction "1_1") (pintype "passive"))
      (node (ref "IC2") (pin "5") (pinfunction "OUT_5") (pintype "output"))
      (node (ref "J2") (pin "3") (pinfunction "3_3") (pintype "passive"))
      (node (ref "J4") (pin "3") (pinfunction "3_3") (pintype "passive"))
      (node (ref "J7") (pin "4") (pinfunction "4_4") (pintype "passive"))
    )
    (net (code "73") (name "VD2") (class "Default")
      (node (ref "C9") (pin "1") (pinfunction "1_1") (pintype "passive"))
      (node (ref "IC3") (pin "5") (pinfunction "OUT_5") (pintype "output"))
      (node (ref "J1") (pin "3") (pinfunction "3_3") (pintype "passive"))
      (node (ref "J3") (pin "3") (pinfunction "3_3") (pintype "passive"))
    )
    (net (code "74") (name "VDD") (class "Default")
      (node (ref "C12") (pin "1") (pinfunction "1_1") (pintype "passive"))
      (node (ref "C14") (pin "1") (pinfunction "1_1") (pintype "passive"))
      (node (ref "C17") (pin "1") (pinfunction "1_1") (pintype "passive"))
      (node (ref "C23") (pin "1") (pinfunction "1_1") (pintype "passive"))
      (node (ref "C24") (pin "1") (pinfunction "1_1") (pintype "passive"))
      (node (ref "C25") (pin "1") (pinfunction "1_1") (pintype "passive"))
      (node (ref "C4") (pin "1") (pinfunction "1_1") (pintype "passive"))
      (node (ref "C5") (pin "1") (pinfunction "1_1") (pintype "passive"))
      (node (ref "C6") (pin "1") (pinfunction "1_1") (pintype "passive"))
      (node (ref "D1") (pin "3") (pinfunction "K_3") (pintype "passive"))
      (node (ref "J20") (pin "3") (pinfunction "3_3") (pintype "passive"))
      (node (ref "L1") (pin "2") (pinfunction "2_2") (pintype "passive"))
      (node (ref "M1") (pin "POS") (pinfunction "POS_POS") (pintype "bidirectional"))
      (node (ref "Q3") (pin "S1") (pinfunction "S_S1") (pintype "bidirectional"))
      (node (ref "Q3") (pin "S2") (pinfunction "S_S2") (pintype "bidirectional"))
      (node (ref "R11") (pin "2") (pinfunction "2_2") (pintype "passive"))
      (node (ref "R12") (pin "2") (pinfunction "2_2") (pintype "passive"))
      (node (ref "R13") (pin "2") (pinfunction "2_2") (pintype "passive"))
      (node (ref "R14") (pin "2") (pinfunction "2_2") (pintype "passive"))
      (node (ref "R15") (pin "2") (pinfunction "2_2") (pintype "passive"))
      (node (ref "R18") (pin "1") (pinfunction "1_1") (pintype "passive"))
      (node (ref "R19") (pin "1") (pinfunction "1_1") (pintype "passive"))
      (node (ref "R20") (pin "2") (pinfunction "2_2") (pintype "passive"))
      (node (ref "R21") (pin "2") (pinfunction "2_2") (pintype "passive"))
      (node (ref "R25") (pin "1") (pinfunction "1_1") (pintype "passive"))
      (node (ref "R26") (pin "2") (pinfunction "2_2") (pintype "passive"))
      (node (ref "R28") (pin "2") (pinfunction "2_2") (pintype "passive"))
      (node (ref "R3") (pin "1") (pinfunction "1_1") (pintype "passive"))
      (node (ref "R32") (pin "2") (pinfunction "2_2") (pintype "passive"))
      (node (ref "R34") (pin "2") (pinfunction "2_2") (pintype "passive"))
      (node (ref "R35") (pin "2") (pinfunction "2_2") (pintype "passive"))
      (node (ref "R36") (pin "2") (pinfunction "2_2") (pintype "passive"))
      (node (ref "R44") (pin "2") (pinfunction "2_2") (pintype "passive"))
      (node (ref "R6") (pin "1") (pinfunction "1_1") (pintype "passive"))
      (node (ref "R8") (pin "2") (pinfunction "2_2") (pintype "passive"))
      (node (ref "R9") (pin "2") (pinfunction "2_2") (pintype "passive"))
      (node (ref "U1") (pin "10") (pinfunction "FB_10") (pintype "bidirectional"))
      (node (ref "U3") (pin "1") (pinfunction "VDD1_1") (pintype "power_in"))
      (node (ref "U4") (pin "17") (pinfunction "AVDD_17") (pintype "power_in"))
      (node (ref "U4") (pin "28") (pinfunction "VDD_2_28") (pintype "power_in"))
      (node (ref "U4") (pin "40") (pinfunction "VDD_40") (pintype "power_in"))
      (node (ref "U5") (pin "5") (pinfunction "VIN_5") (pintype "power_in"))
      (node (ref "U6") (pin "8") (pinfunction "VDD_8") (pintype "power_in"))
    )
    (net (code "75") (name "VM") (class "Default")
      (node (ref "C13") (pin "2") (pinfunction "2_2") (pintype "passive"))
      (node (ref "C18") (pin "1") (pinfunction "1_1") (pintype "passive"))
      (node (ref "J1") (pin "1") (pinfunction "1_1") (pintype "passive"))
      (node (ref "J2") (pin "1") (pinfunction "1_1") (pintype "passive"))
      (node (ref "J3") (pin "1") (pinfunction "1_1") (pintype "passive"))
      (node (ref "J4") (pin "1") (pinfunction "1_1") (pintype "passive"))
      (node (ref "J9") (pin "5") (pinfunction "5_5") (pintype "passive"))
      (node (ref "Q2") (pin "5-8") (pinfunction "D_5-8") (pintype "passive"))
      (node (ref "R1") (pin "2") (pinfunction "2_2") (pintype "passive"))
      (node (ref "R27") (pin "2") (pinfunction "2_2") (pintype "passive"))
      (node (ref "U2") (pin "13") (pinfunction "VBB_13") (pintype "power_in"))
    )
    (net (code "76") (name "unconnected-(IC2-ADJ-Pad4)") (class "Default")
      (node (ref "IC2") (pin "4") (pinfunction "ADJ_4") (pintype "passive"))
    )
    (net (code "77") (name "unconnected-(IC3-ADJ-Pad4)") (class "Default")
      (node (ref "IC3") (pin "4") (pinfunction "ADJ_4") (pintype "passive"))
    )
    (net (code "78") (name "unconnected-(J20-Pad1)") (class "Default")
      (node (ref "J20") (pin "1") (pinfunction "1_1") (pintype "passive"))
    )
    (net (code "79") (name "unconnected-(J20-Pad9)") (class "Default")
      (node (ref "J20") (pin "9") (pinfunction "9_9") (pintype "passive"))
    )
    (net (code "80") (name "unconnected-(J21-Pad2)") (class "Default")
      (node (ref "J21") (pin "2") (pinfunction "2_2") (pintype "passive"))
    )
    (net (code "81") (name "unconnected-(J21-Pad3)") (class "Default")
      (node (ref "J21") (pin "3") (pinfunction "3_3") (pintype "passive"))
    )
    (net (code "82") (name "unconnected-(J21-Pad4)") (class "Default")
      (node (ref "J21") (pin "4") (pinfunction "4_4") (pintype "passive"))
    )
    (net (code "83") (name "unconnected-(U2-OUT1A-Pad16)") (class "Default")
      (node (ref "U2") (pin "16") (pinfunction "OUT1A_16") (pintype "output"))
    )
    (net (code "84") (name "unconnected-(U2-OUT1B-Pad14)") (class "Default")
      (node (ref "U2") (pin "14") (pinfunction "OUT1B_14") (pintype "output"))
    )
    (net (code "85") (name "unconnected-(U2-PadEXP)") (class "Default")
      (node (ref "U2") (pin "EXP") (pinfunction "EXP_EXP") (pintype "passive"))
    )
    (net (code "86") (name "unconnected-(U4-PWM1L1{slash}DAC1LN{slash}RP15{slash}CN11{slash}PMCS1{slash}RB15-Pad15)") (class "Default")
      (node (ref "U4") (pin "15") (pinfunction "PWM1L1/DAC1LN/RP15/CN11/PMCS1/RB15_15") (pintype "bidirectional"))
    )
    (net (code "87") (name "unconnected-(U4-PWM1L2{slash}DAC1RN{slash}RP13{slash}CN13{slash}PMRD{slash}RB13-Pad11)") (class "Default")
      (node (ref "U4") (pin "11") (pinfunction "PWM1L2/DAC1RN/RP13/CN13/PMRD/RB13_11") (pintype "bidirectional"))
    )
    (net (code "88") (name "unconnected-(U4-TMS{slash}PMA10{slash}RA10-Pad12)") (class "Default")
      (node (ref "U4") (pin "12") (pinfunction "TMS/PMA10/RA10_12") (pintype "bidirectional"))
    )
  )
)
